# HBridge.net
KiCad netlist of a schematic drawn in EAGLE
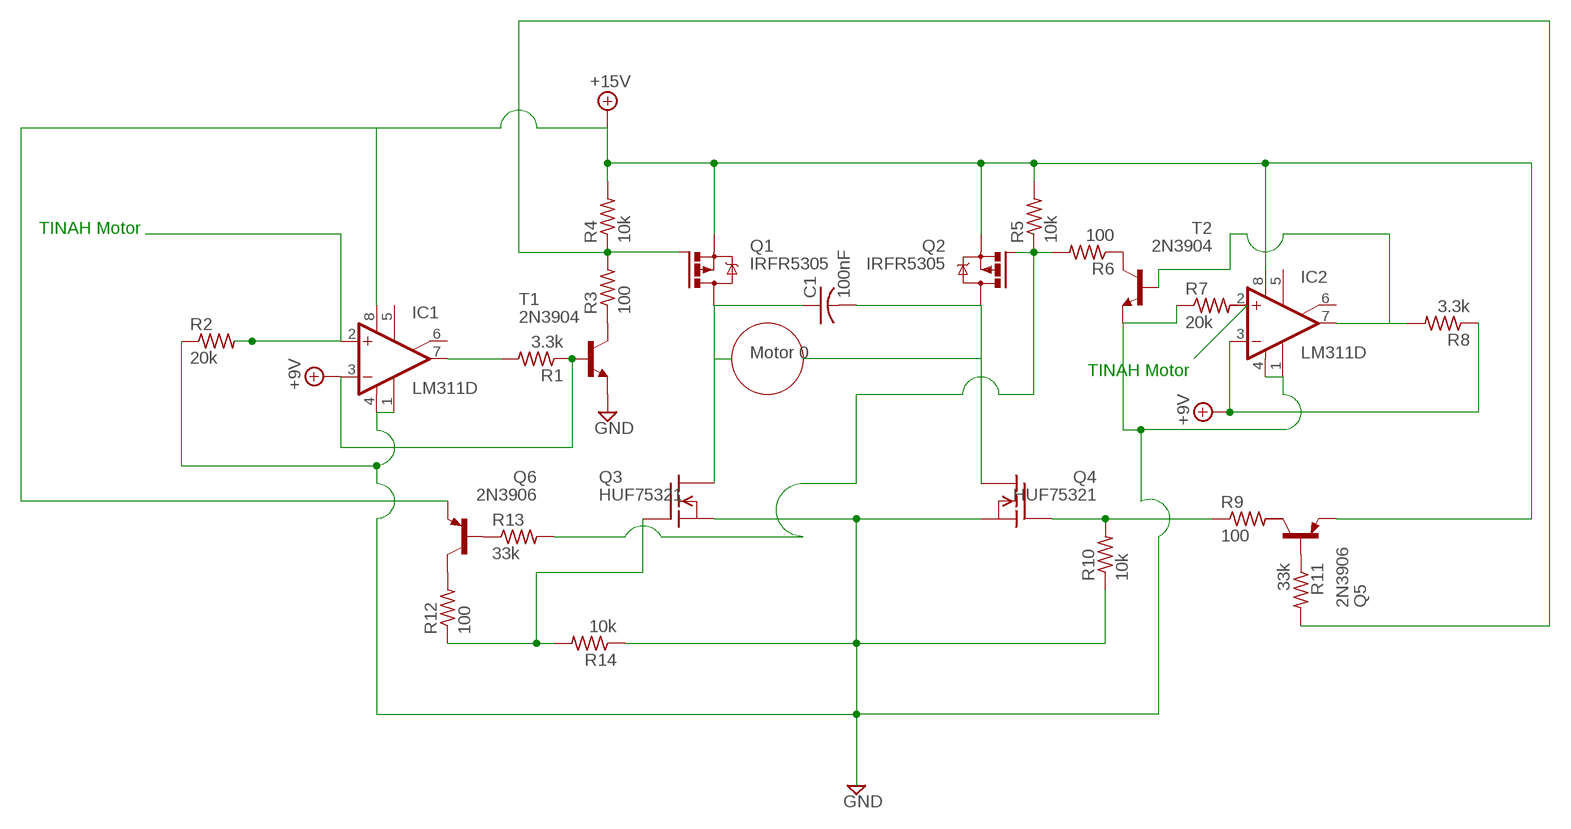
[diagram p0: schematic, sheet 1]

(export (version "E")
  (design (tool "Eeschema 10.0.6"))
  (components
    (comp (ref "C1")
      (value "100nF")
      (footprint "eagle-import:C025-024X044")
      (libsource (lib "eagle-import") (part "C-US025-024X044"))
    )
    (comp (ref "IC1")
      (value "LM311D")
      (footprint "eagle-import:SO08")
      (libsource (lib "eagle-import") (part "LM311D"))
    )
    (comp (ref "IC2")
      (value "LM311D")
      (footprint "eagle-import:SO08")
      (libsource (lib "eagle-import") (part "LM311D"))
    )
    (comp (ref "Q1")
      (value "IRFR5305")
      (footprint "eagle-import:D-PAK_TO252AA")
      (libsource (lib "eagle-import") (part "IRF?5305R"))
    )
    (comp (ref "Q2")
      (value "IRFR5305")
      (footprint "eagle-import:D-PAK_TO252AA")
      (libsource (lib "eagle-import") (part "IRF?5305R"))
    )
    (comp (ref "Q3")
      (value "HUF75321")
      (footprint "eagle-import:SO-8")
      (libsource (lib "eagle-import") (part "FDS5680"))
    )
    (comp (ref "Q4")
      (value "HUF75321")
      (footprint "eagle-import:SO-8")
      (libsource (lib "eagle-import") (part "FDS5680"))
    )
    (comp (ref "Q5")
      (value "2N3906")
      (footprint "eagle-import:TO92")
      (libsource (lib "eagle-import") (part "2N3906"))
    )
    (comp (ref "Q6")
      (value "2N3906")
      (footprint "eagle-import:TO92")
      (libsource (lib "eagle-import") (part "2N3906"))
    )
    (comp (ref "R1")
      (value "3.3k")
      (footprint "eagle-import:0204V")
      (libsource (lib "eagle-import") (part "R-US_0204/2V"))
    )
    (comp (ref "R2")
      (value "20k")
      (footprint "eagle-import:0204V")
      (libsource (lib "eagle-import") (part "R-US_0204/2V"))
    )
    (comp (ref "R3")
      (value "100")
      (footprint "eagle-import:0204V")
      (libsource (lib "eagle-import") (part "R-US_0204/2V"))
    )
    (comp (ref "R4")
      (value "10k")
      (footprint "eagle-import:0204V")
      (libsource (lib "eagle-import") (part "R-US_0204/2V"))
    )
    (comp (ref "R5")
      (value "10k")
      (footprint "eagle-import:0204V")
      (libsource (lib "eagle-import") (part "R-US_0204/2V"))
    )
    (comp (ref "R6")
      (value "100")
      (footprint "eagle-import:0204V")
      (libsource (lib "eagle-import") (part "R-US_0204/2V"))
    )
    (comp (ref "R7")
      (value "20k")
      (footprint "eagle-import:0204V")
      (libsource (lib "eagle-import") (part "R-US_0204/2V"))
    )
    (comp (ref "R8")
      (value "3.3k")
      (footprint "eagle-import:0204V")
      (libsource (lib "eagle-import") (part "R-US_0204/2V"))
    )
    (comp (ref "R9")
      (value "100")
      (footprint "eagle-import:0204V")
      (libsource (lib "eagle-import") (part "R-US_0204/2V"))
    )
    (comp (ref "R10")
      (value "10k")
      (footprint "eagle-import:0204V")
      (libsource (lib "eagle-import") (part "R-US_0204/2V"))
    )
    (comp (ref "R11")
      (value "33k")
      (footprint "eagle-import:0204V")
      (libsource (lib "eagle-import") (part "R-US_0204/2V"))
    )
    (comp (ref "R12")
      (value "100")
      (footprint "eagle-import:0204V")
      (libsource (lib "eagle-import") (part "R-US_0204/2V"))
    )
    (comp (ref "R13")
      (value "33k")
      (footprint "eagle-import:0204V")
      (libsource (lib "eagle-import") (part "R-US_0204/2V"))
    )
    (comp (ref "R14")
      (value "10k")
      (footprint "eagle-import:0204V")
      (libsource (lib "eagle-import") (part "R-US_0204/2V"))
    )
    (comp (ref "T1")
      (value "2N3904")
      (footprint "eagle-import:TO92")
      (libsource (lib "eagle-import") (part "2N3904"))
    )
    (comp (ref "T2")
      (value "2N3904")
      (footprint "eagle-import:TO92")
      (libsource (lib "eagle-import") (part "2N3904"))
    )
  )
  (nets
    (net (code "1") (name "+9V") (class "Default")
      (node (ref "IC1") (pin "3") (pinfunction "-IN_3") (pintype "input"))
      (node (ref "IC2") (pin "3") (pinfunction "-IN_3") (pintype "input"))
      (node (ref "R1") (pin "1") (pinfunction "1_1") (pintype "passive"))
      (node (ref "R8") (pin "1") (pinfunction "1_1") (pintype "passive"))
      (node (ref "T1") (pin "2") (pinfunction "B_2") (pintype "passive"))
    )
    (net (code "2") (name "+15V") (class "Default")
      (node (ref "IC1") (pin "8") (pinfunction "V+_8") (pintype "power_in"))
      (node (ref "IC2") (pin "8") (pinfunction "V+_8") (pintype "power_in"))
      (node (ref "Q1") (pin "3") (pinfunction "S_3") (pintype "passive"))
      (node (ref "Q2") (pin "3") (pinfunction "S_3") (pintype "passive"))
      (node (ref "Q5") (pin "3") (pinfunction "E_3") (pintype "passive"))
      (node (ref "Q6") (pin "3") (pinfunction "E_3") (pintype "passive"))
      (node (ref "R4") (pin "2") (pinfunction "2_2") (pintype "passive"))
      (node (ref "R5") (pin "2") (pinfunction "2_2") (pintype "passive"))
    )
    (net (code "3") (name "GND") (class "Default")
      (node (ref "T1") (pin "3") (pinfunction "E_3") (pintype "passive"))
    )
    (net (code "4") (name "Net-(IC1-+IN)") (class "Default")
      (node (ref "IC1") (pin "2") (pinfunction "+IN_2") (pintype "input"))
      (node (ref "R2") (pin "2") (pinfunction "2_2") (pintype "passive"))
    )
    (net (code "5") (name "Net-(IC1-GND)") (class "Default")
      (node (ref "IC1") (pin "1") (pinfunction "GND_1") (pintype "passive"))
      (node (ref "IC1") (pin "4") (pinfunction "V-_4") (pintype "power_in"))
      (node (ref "IC2") (pin "1") (pinfunction "GND_1") (pintype "passive"))
      (node (ref "IC2") (pin "4") (pinfunction "V-_4") (pintype "power_in"))
      (node (ref "Q3") (pin "1") (pinfunction "S_1") (pintype "passive"))
      (node (ref "Q3") (pin "2") (pinfunction "S_2") (pintype "passive"))
      (node (ref "Q3") (pin "3") (pinfunction "S_3") (pintype "passive"))
      (node (ref "Q4") (pin "1") (pinfunction "S_1") (pintype "passive"))
      (node (ref "Q4") (pin "2") (pinfunction "S_2") (pintype "passive"))
      (node (ref "Q4") (pin "3") (pinfunction "S_3") (pintype "passive"))
      (node (ref "R10") (pin "1") (pinfunction "1_1") (pintype "passive"))
      (node (ref "R14") (pin "1") (pinfunction "1_1") (pintype "passive"))
      (node (ref "R2") (pin "1") (pinfunction "1_1") (pintype "passive"))
      (node (ref "R7") (pin "1") (pinfunction "1_1") (pintype "passive"))
      (node (ref "T2") (pin "3") (pinfunction "E_3") (pintype "passive"))
    )
    (net (code "6") (name "Net-(IC1-OUT)") (class "Default")
      (node (ref "IC1") (pin "7") (pinfunction "OUT_7") (pintype "output"))
      (node (ref "R1") (pin "2") (pinfunction "2_2") (pintype "passive"))
    )
    (net (code "7") (name "Net-(IC2-OUT)") (class "Default")
      (node (ref "IC2") (pin "7") (pinfunction "OUT_7") (pintype "output"))
      (node (ref "R8") (pin "2") (pinfunction "2_2") (pintype "passive"))
      (node (ref "T2") (pin "2") (pinfunction "B_2") (pintype "passive"))
    )
    (net (code "8") (name "Net-(Q1-D)") (class "Default")
      (node (ref "C1") (pin "1") (pinfunction "1_1") (pintype "passive"))
      (node (ref "Q1") (pin "4") (pinfunction "D_4") (pintype "passive"))
      (node (ref "Q3") (pin "5") (pinfunction "D_5") (pintype "passive"))
      (node (ref "Q3") (pin "6") (pinfunction "D_6") (pintype "passive"))
      (node (ref "Q3") (pin "7") (pinfunction "D_7") (pintype "passive"))
      (node (ref "Q3") (pin "8") (pinfunction "D_8") (pintype "passive"))
    )
    (net (code "9") (name "Net-(Q1-G)") (class "Default")
      (node (ref "Q1") (pin "1") (pinfunction "G_1") (pintype "passive"))
      (node (ref "R11") (pin "2") (pinfunction "2_2") (pintype "passive"))
      (node (ref "R3") (pin "2") (pinfunction "2_2") (pintype "passive"))
      (node (ref "R4") (pin "1") (pinfunction "1_1") (pintype "passive"))
    )
    (net (code "10") (name "Net-(Q2-D)") (class "Default")
      (node (ref "C1") (pin "2") (pinfunction "2_2") (pintype "passive"))
      (node (ref "Q2") (pin "4") (pinfunction "D_4") (pintype "passive"))
      (node (ref "Q4") (pin "5") (pinfunction "D_5") (pintype "passive"))
      (node (ref "Q4") (pin "6") (pinfunction "D_6") (pintype "passive"))
      (node (ref "Q4") (pin "7") (pinfunction "D_7") (pintype "passive"))
      (node (ref "Q4") (pin "8") (pinfunction "D_8") (pintype "passive"))
    )
    (net (code "11") (name "Net-(Q2-G)") (class "Default")
      (node (ref "Q2") (pin "1") (pinfunction "G_1") (pintype "passive"))
      (node (ref "R13") (pin "2") (pinfunction "2_2") (pintype "passive"))
      (node (ref "R5") (pin "1") (pinfunction "1_1") (pintype "passive"))
      (node (ref "R6") (pin "2") (pinfunction "2_2") (pintype "passive"))
    )
    (net (code "12") (name "Net-(Q3-G)") (class "Default")
      (node (ref "Q3") (pin "4") (pinfunction "G_4") (pintype "passive"))
      (node (ref "R12") (pin "1") (pinfunction "1_1") (pintype "passive"))
      (node (ref "R14") (pin "2") (pinfunction "2_2") (pintype "passive"))
    )
    (net (code "13") (name "Net-(Q4-G)") (class "Default")
      (node (ref "Q4") (pin "4") (pinfunction "G_4") (pintype "passive"))
      (node (ref "R10") (pin "2") (pinfunction "2_2") (pintype "passive"))
      (node (ref "R9") (pin "1") (pinfunction "1_1") (pintype "passive"))
    )
    (net (code "14") (name "Net-(Q5-B)") (class "Default")
      (node (ref "Q5") (pin "2") (pinfunction "B_2") (pintype "passive"))
      (node (ref "R11") (pin "1") (pinfunction "1_1") (pintype "passive"))
    )
    (net (code "15") (name "Net-(Q6-B)") (class "Default")
      (node (ref "Q6") (pin "2") (pinfunction "B_2") (pintype "passive"))
      (node (ref "R13") (pin "1") (pinfunction "1_1") (pintype "passive"))
    )
    (net (code "16") (name "Net-(Q6-C)") (class "Default")
      (node (ref "Q6") (pin "1") (pinfunction "C_1") (pintype "passive"))
      (node (ref "R12") (pin "2") (pinfunction "2_2") (pintype "passive"))
    )
    (net (code "17") (name "Net-(T1-C)") (class "Default")
      (node (ref "R3") (pin "1") (pinfunction "1_1") (pintype "passive"))
      (node (ref "T1") (pin "1") (pinfunction "C_1") (pintype "passive"))
    )
    (net (code "18") (name "Net-(T2-C)") (class "Default")
      (node (ref "R6") (pin "1") (pinfunction "1_1") (pintype "passive"))
      (node (ref "T2") (pin "1") (pinfunction "C_1") (pintype "passive"))
    )
    (net (code "19") (name "unconnected-(IC1-ON-Pad5)") (class "Default")
      (node (ref "IC1") (pin "5") (pinfunction "ON_5") (pintype "passive"))
    )
    (net (code "20") (name "unconnected-(IC1-ON{slash}STR-Pad6)") (class "Default")
      (node (ref "IC1") (pin "6") (pinfunction "ON/STR_6") (pintype "passive"))
    )
    (net (code "21") (name "unconnected-(IC2-+IN-Pad2)") (class "Default")
      (node (ref "IC2") (pin "2") (pinfunction "+IN_2") (pintype "input"))
    )
    (net (code "22") (name "unconnected-(IC2-ON-Pad5)") (class "Default")
      (node (ref "IC2") (pin "5") (pinfunction "ON_5") (pintype "passive"))
    )
    (net (code "23") (name "unconnected-(IC2-ON{slash}STR-Pad6)") (class "Default")
      (node (ref "IC2") (pin "6") (pinfunction "ON/STR_6") (pintype "passive"))
    )
    (net (code "24") (name "unconnected-(Q5-C-Pad1)") (class "Default")
      (node (ref "Q5") (pin "1") (pinfunction "C_1") (pintype "passive"))
    )
    (net (code "25") (name "unconnected-(R7-Pad2)") (class "Default")
      (node (ref "R7") (pin "2") (pinfunction "2_2") (pintype "passive"))
    )
    (net (code "26") (name "unconnected-(R9-Pad2)") (class "Default")
      (node (ref "R9") (pin "2") (pinfunction "2_2") (pintype "passive"))
    )
  )
)
